# Sheet2.net
KiCad netlist of a schematic drawn in Altium Designer
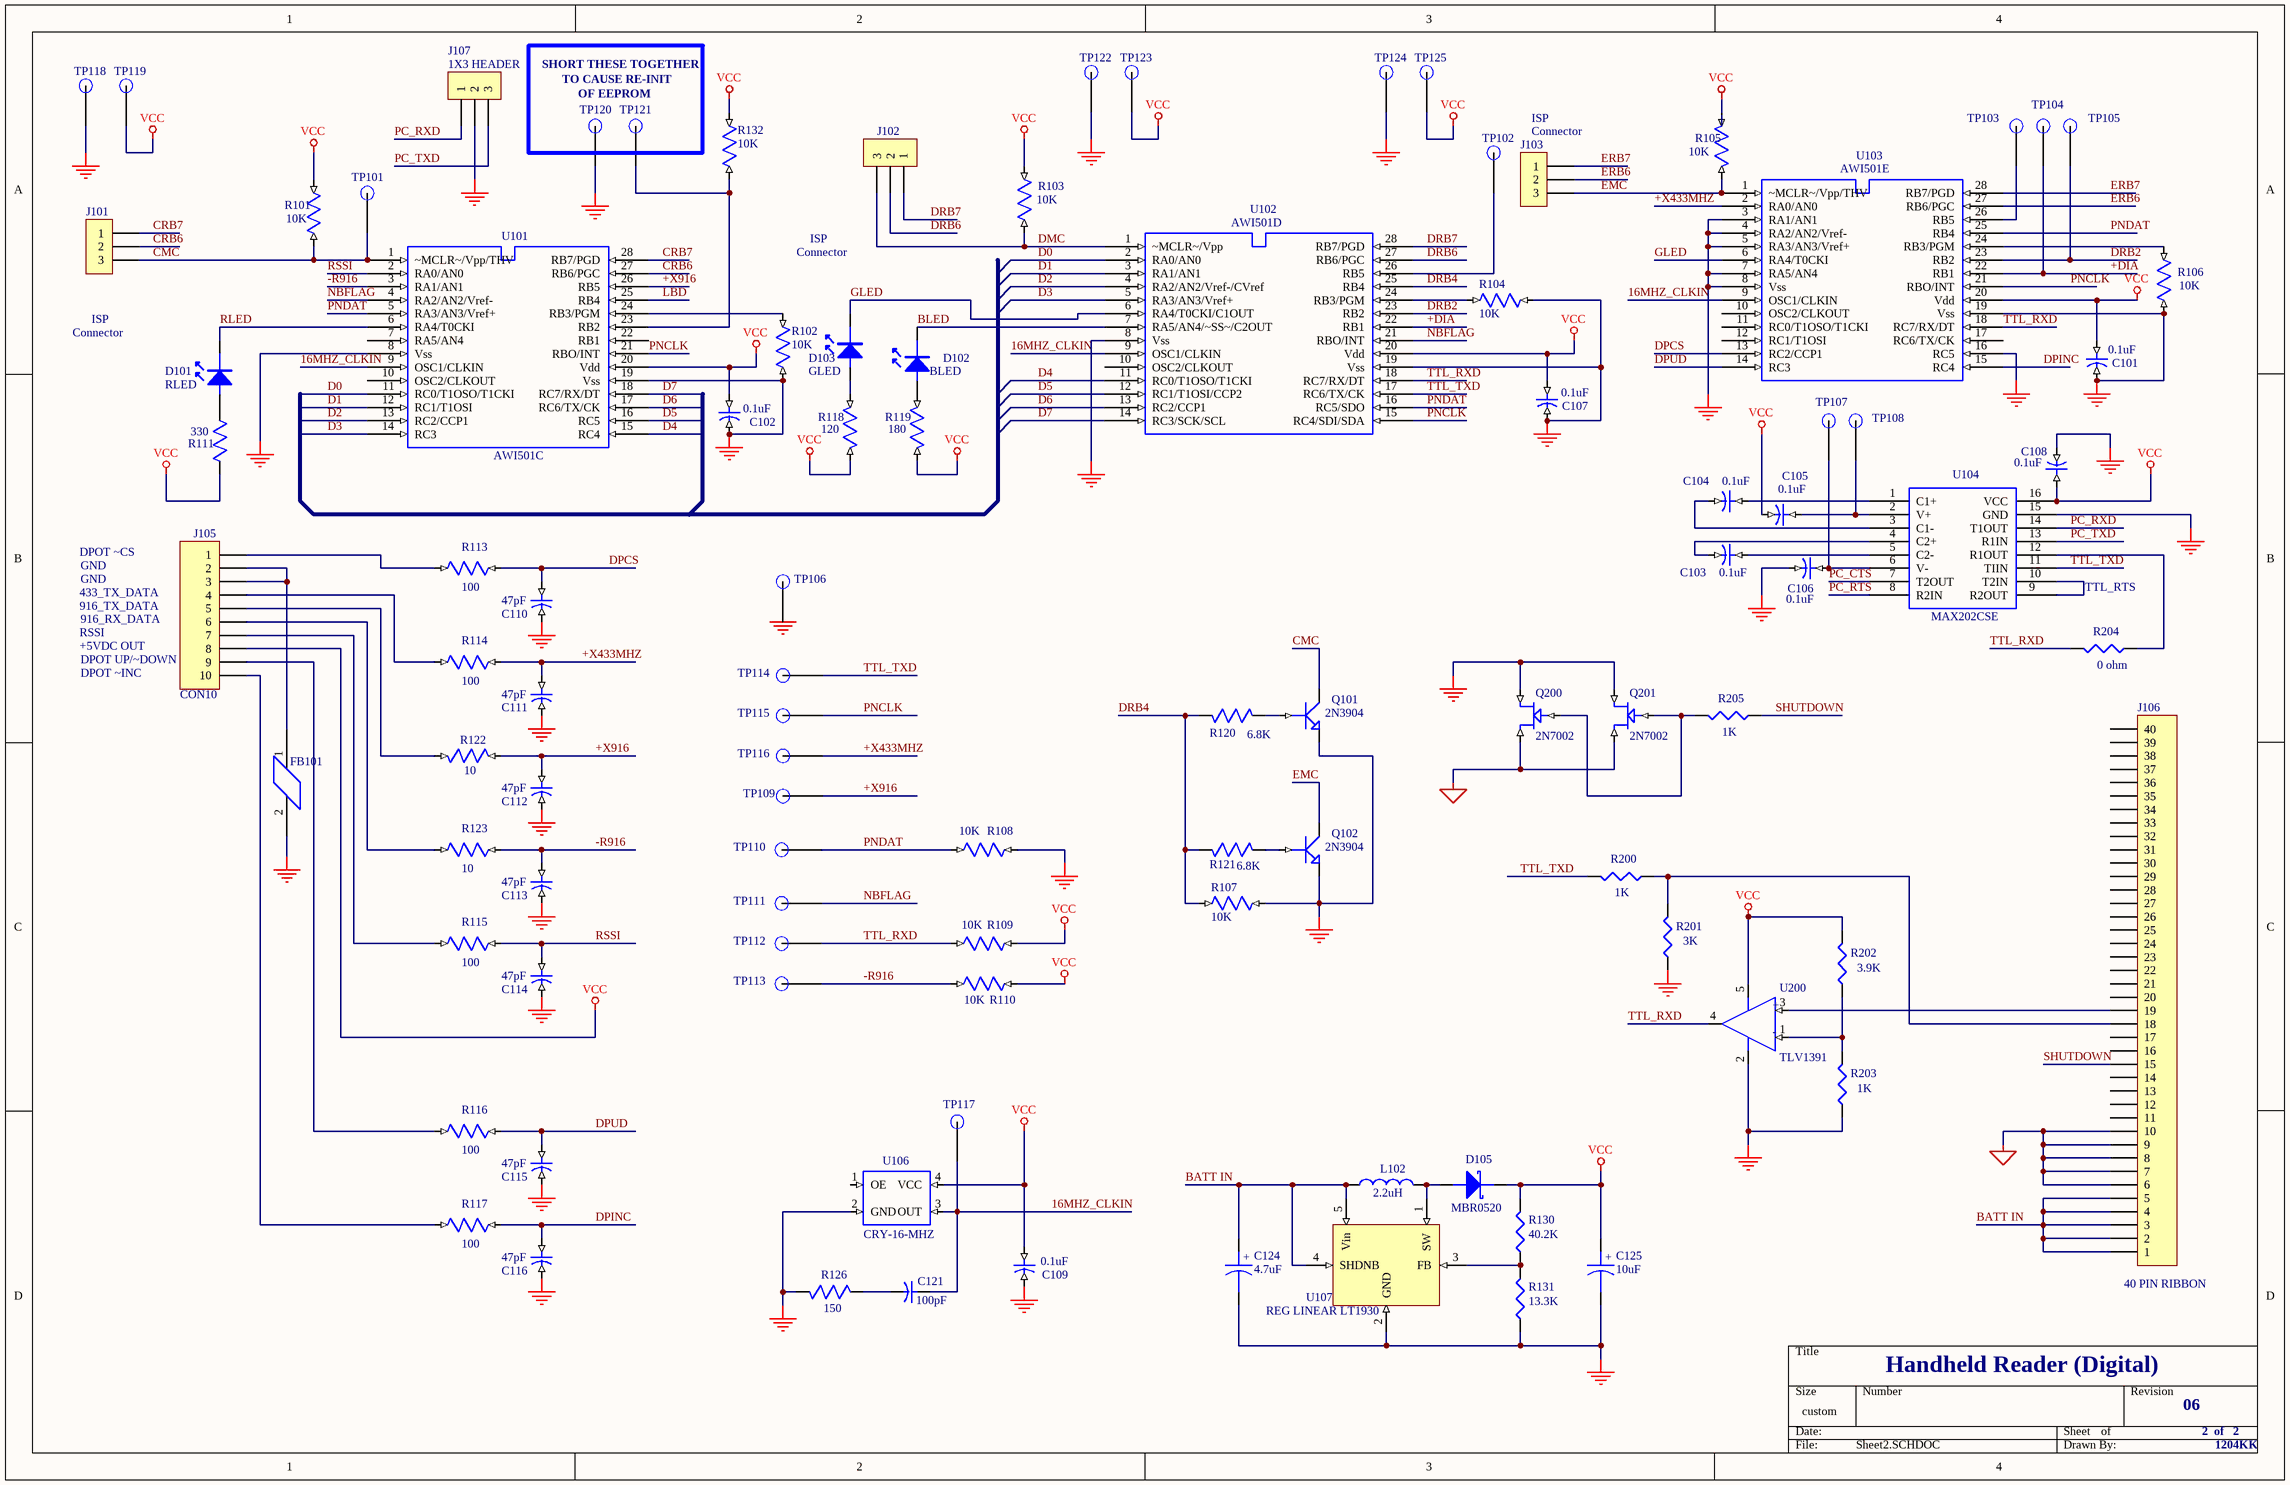
[diagram p0: Sheet2.SCHDOC]

(export (version "E")
  (design (tool "Eeschema 10.0.6"))
  (components
    (comp (ref "C101") (value "0.1uF") (footprint "0603") (libsource (lib "") (part "C_603_1")))
    (comp (ref "C102") (value "0.1uF") (footprint "0603") (libsource (lib "") (part "C_603_1")))
    (comp (ref "C103") (value "0.1uF") (footprint "0603") (libsource (lib "*") (part "C_603")))
    (comp (ref "C104") (value "0.1uF") (footprint "0603") (libsource (lib "*") (part "C_603")))
    (comp (ref "C105") (value "0.1uF") (footprint "0603") (libsource (lib "*") (part "C_603")))
    (comp (ref "C106") (value "0.1uF") (footprint "0603") (libsource (lib "*") (part "C_603")))
    (comp (ref "C107") (value "0.1uF") (footprint "0603") (libsource (lib "") (part "C_603_1")))
    (comp (ref "C108") (value "0.1uF") (footprint "0603") (libsource (lib "*") (part "C_603")))
    (comp (ref "C109") (value "0.1uF") (footprint "0603") (libsource (lib "*") (part "C_603")))
    (comp (ref "C110") (value "47pF") (footprint "0603") (libsource (lib "*") (part "C0603")))
    (comp (ref "C111") (value "47pF") (footprint "0603") (libsource (lib "*") (part "C0603")))
    (comp (ref "C112") (value "47pF") (footprint "0603") (libsource (lib "*") (part "C0603")))
    (comp (ref "C113") (value "47pF") (footprint "0603") (libsource (lib "*") (part "C0603")))
    (comp (ref "C114") (value "47pF") (footprint "0603") (libsource (lib "*") (part "C0603")))
    (comp (ref "C115") (value "47pF") (footprint "0603") (libsource (lib "*") (part "C0603")))
    (comp (ref "C116") (value "47pF") (footprint "0603") (libsource (lib "*") (part "C0603")))
    (comp (ref "C121") (value "100pF") (footprint "0603") (libsource (lib "*") (part "C_0603")))
    (comp (ref "C124")
      (value "4.7uF")
      (footprint "CAP A CASE")
      (description "Capacitor")
      (libsource (lib "*") (part "CAPACITOR POL"))
    )
    (comp (ref "C125")
      (value "10uF")
      (footprint "CAP A CASE")
      (description "Capacitor")
      (libsource (lib "*") (part "CAPACITOR POL"))
    )
    (comp (ref "D101") (value "RLED") (footprint "SOD123 DIODE") (libsource (lib "*") (part "LED")))
    (comp (ref "D102") (value "BLED") (footprint "SOD123 DIODE") (libsource (lib "*") (part "LED")))
    (comp (ref "D103") (value "GLED") (footprint "SOD123 DIODE") (libsource (lib "*") (part "LED")))
    (comp (ref "D105")
      (value "MBR0520")
      (footprint "SOD123")
      (description "Schottky Diode")
      (libsource (lib "*") (part "DIODE SCHOTTKY"))
    )
    (comp (ref "FB101") (value "FB 0603") (footprint "0603") (libsource (lib "*") (part "FB_0603")))
    (comp (ref "J101")
      (value "1X3 HEADER")
      (footprint "1X3 HEADER")
      (description "Connector")
      (libsource (lib "*") (part "CON3"))
    )
    (comp (ref "J102")
      (value "1X3 HEADER")
      (footprint "1X3 HEADER")
      (description "Connector")
      (libsource (lib "") (part "CON3_2"))
    )
    (comp (ref "J103")
      (value "1X3 HEADER")
      (footprint "1X3 HEADER")
      (description "Connector")
      (libsource (lib "*") (part "CON3"))
    )
    (comp (ref "J105")
      (value "CON10")
      (footprint "1X10 HEADER SPECIAL")
      (description "Connector")
      (libsource (lib "*") (part "CON10"))
    )
    (comp (ref "J106")
      (value "40 PIN RIBBON")
      (footprint "40 PIN RIBBON CONN")
      (description "Connector")
      (libsource (lib "*") (part "CON40"))
    )
    (comp (ref "J107")
      (value "1X3 HEADER")
      (footprint "1X3 HEADER")
      (description "Connector")
      (libsource (lib "") (part "CON3_1"))
    )
    (comp (ref "L102")
      (value "2.2uH")
      (footprint "COIL BOURNS SDR7030-330M")
      (libsource (lib "*") (part "INDUCTOR1"))
    )
    (comp (ref "Q101")
      (value "2N3904")
      (footprint "SOT23 TRANS")
      (description "NPN Transistor")
      (libsource (lib "*") (part "NPN1"))
    )
    (comp (ref "Q102")
      (value "2N3904")
      (footprint "SOT23 TRANS")
      (description "NPN Transistor")
      (libsource (lib "*") (part "NPN1"))
    )
    (comp (ref "Q200") (value "2N7002") (footprint "SOT23 FET") (libsource (lib "*") (part "JFET N")))
    (comp (ref "Q201") (value "2N7002") (footprint "SOT23 FET") (libsource (lib "*") (part "JFET N")))
    (comp (ref "R101") (value "10K") (footprint "0603") (libsource (lib "*") (part "R_603")))
    (comp (ref "R102") (value "10K") (footprint "0603") (libsource (lib "*") (part "R_603")))
    (comp (ref "R103") (value "10K") (footprint "0603") (libsource (lib "*") (part "R_603")))
    (comp (ref "R104") (value "10K") (footprint "0603") (libsource (lib "*") (part "R_603")))
    (comp (ref "R105") (value "10K") (footprint "0603") (libsource (lib "*") (part "R_603")))
    (comp (ref "R106") (value "10K") (footprint "0603") (libsource (lib "*") (part "R_603")))
    (comp (ref "R107") (value "10K") (footprint "0603") (libsource (lib "*") (part "R_603")))
    (comp (ref "R108") (value "10K") (footprint "0603") (libsource (lib "*") (part "R_603")))
    (comp (ref "R109") (value "10K") (footprint "0603") (libsource (lib "*") (part "R_603")))
    (comp (ref "R110") (value "10K") (footprint "0603") (libsource (lib "*") (part "R_603")))
    (comp (ref "R111") (value "330") (footprint "0603") (libsource (lib "*") (part "R_0603")))
    (comp (ref "R113") (value "100") (footprint "0603") (libsource (lib "*") (part "R0603")))
    (comp (ref "R114") (value "100") (footprint "0603") (libsource (lib "*") (part "R0603")))
    (comp (ref "R115") (value "100") (footprint "0603") (libsource (lib "*") (part "R0603")))
    (comp (ref "R116") (value "100") (footprint "0603") (libsource (lib "*") (part "R0603")))
    (comp (ref "R117") (value "100") (footprint "0603") (libsource (lib "*") (part "R0603")))
    (comp (ref "R118") (value "120") (footprint "0603") (libsource (lib "*") (part "R0402")))
    (comp (ref "R119") (value "180") (footprint "0603") (libsource (lib "*") (part "R0402")))
    (comp (ref "R120") (value "6.8K") (footprint "0603") (libsource (lib "*") (part "R_0603")))
    (comp (ref "R121") (value "6.8K") (footprint "0603") (libsource (lib "*") (part "R_0603")))
    (comp (ref "R122") (value "10") (footprint "0603") (libsource (lib "*") (part "R_603")))
    (comp (ref "R123") (value "10") (footprint "0603") (libsource (lib "*") (part "R0603")))
    (comp (ref "R126") (value "150") (footprint "0603") (libsource (lib "*") (part "R_0603")))
    (comp (ref "R130") (value "40.2K") (footprint "0603") (libsource (lib "*") (part "RES1")))
    (comp (ref "R131") (value "13.3K") (footprint "0603") (libsource (lib "*") (part "RES1")))
    (comp (ref "R132") (value "10K") (footprint "0603") (libsource (lib "*") (part "R_603")))
    (comp (ref "R200") (value "1K") (footprint "0603") (libsource (lib "*") (part "RES1")))
    (comp (ref "R201") (value "3K") (footprint "0603") (libsource (lib "*") (part "RES1")))
    (comp (ref "R202") (value "3.9K") (footprint "0603") (libsource (lib "*") (part "RES1")))
    (comp (ref "R203") (value "1K") (footprint "0603") (libsource (lib "*") (part "RES1")))
    (comp (ref "R204") (value "0 ohm") (footprint "0603") (libsource (lib "*") (part "RES1")))
    (comp (ref "R205") (value "1K") (footprint "0603") (libsource (lib "*") (part "RES1")))
    (comp (ref "TP101") (value "TP") (footprint "TEST POINT PAD") (libsource (lib "*") (part "TESTPOINT_1")))
    (comp (ref "TP102") (value "TP") (footprint "TEST POINT PAD") (libsource (lib "*") (part "TESTPOINT_1")))
    (comp (ref "TP103") (value "TP") (footprint "TEST POINT PAD") (libsource (lib "*") (part "TESTPOINT_1")))
    (comp (ref "TP104") (value "TP") (footprint "TEST POINT PAD") (libsource (lib "*") (part "TESTPOINT_1")))
    (comp (ref "TP105") (value "TP") (footprint "TEST POINT PAD") (libsource (lib "*") (part "TESTPOINT_1")))
    (comp (ref "TP106") (value "TP") (footprint "TEST POINT PAD") (libsource (lib "*") (part "TESTPOINT_1")))
    (comp (ref "TP107") (value "TP") (footprint "TEST POINT PAD") (libsource (lib "*") (part "TESTPOINT_1")))
    (comp (ref "TP108") (value "TP") (footprint "TEST POINT PAD") (libsource (lib "*") (part "TESTPOINT_1")))
    (comp (ref "TP109") (value "TP") (footprint "TEST POINT PAD") (libsource (lib "*") (part "TESTPOINT_1")))
    (comp (ref "TP110") (value "TP") (footprint "TEST POINT PAD") (libsource (lib "*") (part "TESTPOINT_1")))
    (comp (ref "TP111") (value "TP") (footprint "TEST POINT PAD") (libsource (lib "*") (part "TESTPOINT_1")))
    (comp (ref "TP112") (value "TP") (footprint "TEST POINT PAD") (libsource (lib "*") (part "TESTPOINT_1")))
    (comp (ref "TP113") (value "TP") (footprint "TEST POINT PAD") (libsource (lib "*") (part "TESTPOINT_1")))
    (comp (ref "TP114") (value "TP") (footprint "TEST POINT PAD") (libsource (lib "*") (part "TESTPOINT_1")))
    (comp (ref "TP115") (value "TP") (footprint "TEST POINT PAD") (libsource (lib "*") (part "TESTPOINT_1")))
    (comp (ref "TP116") (value "TP") (footprint "TEST POINT PAD") (libsource (lib "*") (part "TESTPOINT_1")))
    (comp (ref "TP117") (value "TP") (footprint "TEST POINT PAD") (libsource (lib "*") (part "TESTPOINT_1")))
    (comp (ref "TP118") (value "TP") (footprint "TEST POINT PAD") (libsource (lib "*") (part "TESTPOINT_1")))
    (comp (ref "TP119") (value "TP") (footprint "TEST POINT PAD") (libsource (lib "*") (part "TESTPOINT_1")))
    (comp (ref "TP120") (value "TP") (footprint "TEST POINT PAD") (libsource (lib "*") (part "TESTPOINT_1")))
    (comp (ref "TP121") (value "TP") (footprint "TEST POINT PAD") (libsource (lib "*") (part "TESTPOINT_1")))
    (comp (ref "TP122") (value "TP") (footprint "TEST POINT PAD") (libsource (lib "*") (part "TESTPOINT_1")))
    (comp (ref "TP123") (value "TP") (footprint "TEST POINT PAD") (libsource (lib "*") (part "TESTPOINT_1")))
    (comp (ref "TP124") (value "TP") (footprint "TEST POINT PAD") (libsource (lib "*") (part "TESTPOINT_1")))
    (comp (ref "TP125") (value "TP") (footprint "TEST POINT PAD") (libsource (lib "*") (part "TESTPOINT_1")))
    (comp (ref "U101") (value "AWI501C") (footprint "SSOP28") (libsource (lib "*") (part "PIC16F870")))
    (comp (ref "U102") (value "AWI501D") (footprint "SSOP28") (libsource (lib "*") (part "PIC16F876A")))
    (comp (ref "U103") (value "AWI501E") (footprint "SSOP28") (libsource (lib "*") (part "PIC16F870")))
    (comp (ref "U104") (value "MAX202CSE") (footprint "SO16") (libsource (lib "*") (part "MAX202CSE")))
    (comp (ref "U106")
      (value "CRY-16-MHZ")
      (footprint "SMT OSCILLATOR")
      (libsource (lib "*") (part "CRY-SMD-5-7"))
    )
    (comp (ref "U107")
      (value "REG LINEAR LT1930")
      (footprint "SOT23-5A")
      (libsource (lib "*") (part "REG LINEAR LT1930"))
    )
    (comp (ref "U200") (value "TLV1391") (footprint "SOT25") (libsource (lib "*") (part "TLV1391")))
  )
  (nets
    (net (code "1") (name "/+DIA") (class "Default")
      (node (ref "TP104") (pin "1") (pinfunction "TP_1") (pintype "passive"))
      (node (ref "U102") (pin "22") (pinfunction "RB1_22") (pintype "input"))
      (node (ref "U103") (pin "22") (pinfunction "RB1_22") (pintype "input"))
    )
    (net (code "2") (name "/+X433MHZ") (class "Default")
      (node (ref "C111") (pin "1") (pinfunction "A_1") (pintype "input"))
      (node (ref "R114") (pin "2") (pinfunction "B_2") (pintype "input"))
      (node (ref "TP116") (pin "1") (pinfunction "TP_1") (pintype "passive"))
      (node (ref "U103") (pin "2") (pinfunction "RA0/AN0_2") (pintype "input"))
    )
    (net (code "3") (name "/+X916") (class "Default")
      (node (ref "C112") (pin "1") (pinfunction "A_1") (pintype "input"))
      (node (ref "R122") (pin "1") (pinfunction "A_1") (pintype "input"))
      (node (ref "TP109") (pin "1") (pinfunction "TP_1") (pintype "passive"))
      (node (ref "U101") (pin "26") (pinfunction "RB5_26") (pintype "input"))
    )
    (net (code "4") (name "/-R916") (class "Default")
      (node (ref "C113") (pin "1") (pinfunction "A_1") (pintype "input"))
      (node (ref "R110") (pin "2") (pinfunction "B_2") (pintype "input"))
      (node (ref "R123") (pin "2") (pinfunction "B_2") (pintype "input"))
      (node (ref "TP113") (pin "1") (pinfunction "TP_1") (pintype "passive"))
      (node (ref "U101") (pin "3") (pinfunction "RA1/AN1_3") (pintype "input"))
    )
    (net (code "5") (name "/16MHZ_CLKIN") (class "Default")
      (node (ref "C121") (pin "1") (pinfunction "A_1") (pintype "passive"))
      (node (ref "TP117") (pin "1") (pinfunction "TP_1") (pintype "passive"))
      (node (ref "U101") (pin "9") (pinfunction "OSC1/CLKIN_9") (pintype "input"))
      (node (ref "U102") (pin "9") (pinfunction "OSC1/CLKIN_9") (pintype "input"))
      (node (ref "U103") (pin "9") (pinfunction "OSC1/CLKIN_9") (pintype "input"))
      (node (ref "U106") (pin "3") (pinfunction "OUT_3") (pintype "input"))
    )
    (net (code "6") (name "/BATT IN") (class "Default")
      (node (ref "C124") (pin "1") (pinfunction "1_1") (pintype "passive"))
      (node (ref "J106") (pin "1") (pinfunction "1_1") (pintype "passive"))
      (node (ref "J106") (pin "2") (pinfunction "2_2") (pintype "passive"))
      (node (ref "J106") (pin "3") (pinfunction "3_3") (pintype "passive"))
      (node (ref "J106") (pin "4") (pinfunction "4_4") (pintype "passive"))
      (node (ref "J106") (pin "5") (pinfunction "5_5") (pintype "passive"))
      (node (ref "L102") (pin "1") (pinfunction "1_1") (pintype "passive"))
      (node (ref "U107") (pin "4") (pinfunction "SHDNB_4") (pintype "input"))
      (node (ref "U107") (pin "5") (pinfunction "Vin_5") (pintype "input"))
    )
    (net (code "7") (name "/BLED") (class "Default")
      (node (ref "D102") (pin "K") (pinfunction "K_K") (pintype "passive"))
      (node (ref "U102") (pin "7") (pinfunction "RA5/AN4/~SS~/C2OUT_7") (pintype "input"))
    )
    (net (code "8") (name "/CMC") (class "Default")
      (node (ref "J101") (pin "3") (pinfunction "3_3") (pintype "passive"))
      (node (ref "Q101") (pin "C") (pinfunction "C_C") (pintype "passive"))
      (node (ref "R101") (pin "2") (pinfunction "B_2") (pintype "input"))
      (node (ref "TP101") (pin "1") (pinfunction "TP_1") (pintype "passive"))
      (node (ref "U101") (pin "1") (pinfunction "~MCLR~/Vpp/THV_1") (pintype "input"))
    )
    (net (code "9") (name "/CRB6") (class "Default")
      (node (ref "J101") (pin "2") (pinfunction "2_2") (pintype "passive"))
      (node (ref "U101") (pin "27") (pinfunction "RB6/PGC_27") (pintype "input"))
    )
    (net (code "10") (name "/CRB7") (class "Default")
      (node (ref "J101") (pin "1") (pinfunction "1_1") (pintype "passive"))
      (node (ref "U101") (pin "28") (pinfunction "RB7/PGD_28") (pintype "input"))
    )
    (net (code "11") (name "/D0") (class "Default")
      (node (ref "U101") (pin "11") (pinfunction "RC0/T1OSO/T1CKI_11") (pintype "input"))
      (node (ref "U102") (pin "2") (pinfunction "RA0/AN0_2") (pintype "input"))
    )
    (net (code "12") (name "/D1") (class "Default")
      (node (ref "U101") (pin "12") (pinfunction "RC1/T1OSI_12") (pintype "input"))
      (node (ref "U102") (pin "3") (pinfunction "RA1/AN1_3") (pintype "input"))
    )
    (net (code "13") (name "/D2") (class "Default")
      (node (ref "U101") (pin "13") (pinfunction "RC2/CCP1_13") (pintype "input"))
      (node (ref "U102") (pin "4") (pinfunction "RA2/AN2/Vref-/CVref_4") (pintype "input"))
    )
    (net (code "14") (name "/D3") (class "Default")
      (node (ref "U101") (pin "14") (pinfunction "RC3_14") (pintype "input"))
      (node (ref "U102") (pin "5") (pinfunction "RA3/AN3/Vref+_5") (pintype "input"))
    )
    (net (code "15") (name "/D4") (class "Default")
      (node (ref "U101") (pin "15") (pinfunction "RC4_15") (pintype "input"))
      (node (ref "U102") (pin "11") (pinfunction "RC0/T1OSO/T1CKI_11") (pintype "input"))
    )
    (net (code "16") (name "/D5") (class "Default")
      (node (ref "U101") (pin "16") (pinfunction "RC5_16") (pintype "input"))
      (node (ref "U102") (pin "12") (pinfunction "RC1/T1OSI/CCP2_12") (pintype "input"))
    )
    (net (code "17") (name "/D6") (class "Default")
      (node (ref "U101") (pin "17") (pinfunction "RC6/TX/CK_17") (pintype "input"))
      (node (ref "U102") (pin "13") (pinfunction "RC2/CCP1_13") (pintype "input"))
    )
    (net (code "18") (name "/D7") (class "Default")
      (node (ref "U101") (pin "18") (pinfunction "RC7/RX/DT_18") (pintype "input"))
      (node (ref "U102") (pin "14") (pinfunction "RC3/SCK/SCL_14") (pintype "input"))
    )
    (net (code "19") (name "/DMC") (class "Default")
      (node (ref "J102") (pin "3") (pinfunction "3_3") (pintype "passive"))
      (node (ref "R103") (pin "2") (pinfunction "B_2") (pintype "input"))
      (node (ref "U102") (pin "1") (pinfunction "~MCLR~/Vpp_1") (pintype "input"))
    )
    (net (code "20") (name "/DPCS") (class "Default")
      (node (ref "C110") (pin "1") (pinfunction "A_1") (pintype "input"))
      (node (ref "R113") (pin "2") (pinfunction "B_2") (pintype "input"))
      (node (ref "U103") (pin "13") (pinfunction "RC2/CCP1_13") (pintype "input"))
    )
    (net (code "21") (name "/DPINC") (class "Default")
      (node (ref "C116") (pin "1") (pinfunction "A_1") (pintype "input"))
      (node (ref "R117") (pin "2") (pinfunction "B_2") (pintype "input"))
      (node (ref "U103") (pin "15") (pinfunction "RC4_15") (pintype "input"))
    )
    (net (code "22") (name "/DPUD") (class "Default")
      (node (ref "C115") (pin "1") (pinfunction "A_1") (pintype "input"))
      (node (ref "R116") (pin "2") (pinfunction "B_2") (pintype "input"))
      (node (ref "U103") (pin "14") (pinfunction "RC3_14") (pintype "input"))
    )
    (net (code "23") (name "/DRB2") (class "Default")
      (node (ref "TP105") (pin "1") (pinfunction "TP_1") (pintype "passive"))
      (node (ref "U102") (pin "23") (pinfunction "RB2_23") (pintype "input"))
      (node (ref "U103") (pin "23") (pinfunction "RB2_23") (pintype "input"))
    )
    (net (code "24") (name "/DRB4") (class "Default")
      (node (ref "R107") (pin "1") (pinfunction "A_1") (pintype "input"))
      (node (ref "R120") (pin "1") (pinfunction "A_1") (pintype "passive"))
      (node (ref "R121") (pin "1") (pinfunction "A_1") (pintype "passive"))
      (node (ref "U102") (pin "25") (pinfunction "RB4_25") (pintype "input"))
    )
    (net (code "25") (name "/DRB6") (class "Default")
      (node (ref "J102") (pin "2") (pinfunction "2_2") (pintype "passive"))
      (node (ref "U102") (pin "27") (pinfunction "RB6/PGC_27") (pintype "input"))
    )
    (net (code "26") (name "/DRB7") (class "Default")
      (node (ref "J102") (pin "1") (pinfunction "1_1") (pintype "passive"))
      (node (ref "U102") (pin "28") (pinfunction "RB7/PGD_28") (pintype "input"))
    )
    (net (code "27") (name "/EMC") (class "Default")
      (node (ref "J103") (pin "3") (pinfunction "3_3") (pintype "passive"))
      (node (ref "Q102") (pin "C") (pinfunction "C_C") (pintype "passive"))
      (node (ref "R105") (pin "2") (pinfunction "B_2") (pintype "input"))
      (node (ref "U103") (pin "1") (pinfunction "~MCLR~/Vpp/THV_1") (pintype "input"))
    )
    (net (code "28") (name "/ERB6") (class "Default")
      (node (ref "J103") (pin "2") (pinfunction "2_2") (pintype "passive"))
      (node (ref "U103") (pin "27") (pinfunction "RB6/PGC_27") (pintype "input"))
    )
    (net (code "29") (name "/ERB7") (class "Default")
      (node (ref "J103") (pin "1") (pinfunction "1_1") (pintype "passive"))
      (node (ref "U103") (pin "28") (pinfunction "RB7/PGD_28") (pintype "input"))
    )
    (net (code "30") (name "/GLED") (class "Default")
      (node (ref "D103") (pin "K") (pinfunction "K_K") (pintype "passive"))
      (node (ref "U102") (pin "6") (pinfunction "RA4/T0CKI/C1OUT_6") (pintype "input"))
      (node (ref "U103") (pin "6") (pinfunction "RA4/T0CKI_6") (pintype "input"))
    )
    (net (code "31") (name "/LBD") (class "Default")
      (node (ref "U101") (pin "25") (pinfunction "RB4_25") (pintype "input"))
    )
    (net (code "32") (name "/NBFLAG") (class "Default")
      (node (ref "TP111") (pin "1") (pinfunction "TP_1") (pintype "passive"))
      (node (ref "U101") (pin "4") (pinfunction "RA2/AN2/Vref-_4") (pintype "input"))
      (node (ref "U102") (pin "21") (pinfunction "RBO/INT_21") (pintype "input"))
    )
    (net (code "33") (name "/PC_CTS") (class "Default")
      (node (ref "U104") (pin "7") (pinfunction "T2OUT_7") (pintype "passive"))
    )
    (net (code "34") (name "/PC_RTS") (class "Default")
      (node (ref "U104") (pin "8") (pinfunction "R2IN_8") (pintype "passive"))
    )
    (net (code "35") (name "/PC_RXD") (class "Default")
      (node (ref "J107") (pin "1") (pinfunction "1_1") (pintype "passive"))
      (node (ref "U104") (pin "14") (pinfunction "T1OUT_14") (pintype "passive"))
    )
    (net (code "36") (name "/PC_TXD") (class "Default")
      (node (ref "J107") (pin "3") (pinfunction "3_3") (pintype "passive"))
      (node (ref "U104") (pin "13") (pinfunction "R1IN_13") (pintype "passive"))
    )
    (net (code "37") (name "/PNCLK") (class "Default")
      (node (ref "TP115") (pin "1") (pinfunction "TP_1") (pintype "passive"))
      (node (ref "U101") (pin "21") (pinfunction "RBO/INT_21") (pintype "input"))
      (node (ref "U102") (pin "15") (pinfunction "RC4/SDI/SDA_15") (pintype "input"))
      (node (ref "U103") (pin "21") (pinfunction "RBO/INT_21") (pintype "input"))
    )
    (net (code "38") (name "/PNDAT") (class "Default")
      (node (ref "R108") (pin "2") (pinfunction "B_2") (pintype "input"))
      (node (ref "TP110") (pin "1") (pinfunction "TP_1") (pintype "passive"))
      (node (ref "U101") (pin "5") (pinfunction "RA3/AN3/Vref+_5") (pintype "input"))
      (node (ref "U102") (pin "16") (pinfunction "RC5/SDO_16") (pintype "input"))
      (node (ref "U103") (pin "25") (pinfunction "RB4_25") (pintype "input"))
    )
    (net (code "39") (name "/RLED") (class "Default")
      (node (ref "D101") (pin "K") (pinfunction "K_K") (pintype "passive"))
      (node (ref "U101") (pin "6") (pinfunction "RA4/T0CKI_6") (pintype "input"))
    )
    (net (code "40") (name "/RSSI") (class "Default")
      (node (ref "C114") (pin "1") (pinfunction "A_1") (pintype "input"))
      (node (ref "R115") (pin "2") (pinfunction "B_2") (pintype "input"))
      (node (ref "U101") (pin "2") (pinfunction "RA0/AN0_2") (pintype "input"))
    )
    (net (code "41") (name "/SHUTDOWN") (class "Default")
      (node (ref "J106") (pin "15") (pinfunction "15_15") (pintype "passive"))
      (node (ref "R205") (pin "1") (pinfunction "1_1") (pintype "passive"))
    )
    (net (code "42") (name "/TTL_RXD") (class "Default")
      (node (ref "R109") (pin "2") (pinfunction "B_2") (pintype "input"))
      (node (ref "R204") (pin "2") (pinfunction "2_2") (pintype "passive"))
      (node (ref "TP112") (pin "1") (pinfunction "TP_1") (pintype "passive"))
      (node (ref "U102") (pin "18") (pinfunction "RC7/RX/DT_18") (pintype "input"))
      (node (ref "U103") (pin "18") (pinfunction "RC7/RX/DT_18") (pintype "input"))
      (node (ref "U200") (pin "4") (pinfunction "OUT_4") (pintype "open_collector"))
    )
    (net (code "43") (name "/TTL_TXD") (class "Default")
      (node (ref "R200") (pin "2") (pinfunction "2_2") (pintype "passive"))
      (node (ref "TP114") (pin "1") (pinfunction "TP_1") (pintype "passive"))
      (node (ref "U102") (pin "17") (pinfunction "RC6/TX/CK_17") (pintype "input"))
      (node (ref "U104") (pin "11") (pinfunction "TIIN_11") (pintype "passive"))
    )
    (net (code "44") (name "GND1") (class "Default")
      (node (ref "J106") (pin "10") (pinfunction "10_10") (pintype "passive"))
      (node (ref "J106") (pin "6") (pinfunction "6_6") (pintype "passive"))
      (node (ref "J106") (pin "7") (pinfunction "7_7") (pintype "passive"))
      (node (ref "J106") (pin "8") (pinfunction "8_8") (pintype "passive"))
      (node (ref "J106") (pin "9") (pinfunction "9_9") (pintype "passive"))
      (node (ref "Q200") (pin "S") (pinfunction "S_S") (pintype "input"))
      (node (ref "Q201") (pin "S") (pinfunction "S_S") (pintype "input"))
    )
    (net (code "45") (name "GND_COM") (class "Default")
      (node (ref "C101") (pin "2") (pinfunction "B_2") (pintype "input"))
      (node (ref "C102") (pin "2") (pinfunction "B_2") (pintype "input"))
      (node (ref "C106") (pin "2") (pinfunction "B_2") (pintype "input"))
      (node (ref "C107") (pin "2") (pinfunction "B_2") (pintype "input"))
      (node (ref "C108") (pin "2") (pinfunction "B_2") (pintype "input"))
      (node (ref "C109") (pin "2") (pinfunction "B_2") (pintype "input"))
      (node (ref "C110") (pin "2") (pinfunction "B_2") (pintype "input"))
      (node (ref "C111") (pin "2") (pinfunction "B_2") (pintype "input"))
      (node (ref "C112") (pin "2") (pinfunction "B_2") (pintype "input"))
      (node (ref "C113") (pin "2") (pinfunction "B_2") (pintype "input"))
      (node (ref "C114") (pin "2") (pinfunction "B_2") (pintype "input"))
      (node (ref "C115") (pin "2") (pinfunction "B_2") (pintype "input"))
      (node (ref "C116") (pin "2") (pinfunction "B_2") (pintype "input"))
      (node (ref "C124") (pin "2") (pinfunction "2_2") (pintype "passive"))
      (node (ref "C125") (pin "2") (pinfunction "2_2") (pintype "passive"))
      (node (ref "FB101") (pin "2") (pinfunction "1_2") (pintype "passive"))
      (node (ref "J107") (pin "2") (pinfunction "2_2") (pintype "passive"))
      (node (ref "Q101") (pin "E") (pinfunction "E_E") (pintype "passive"))
      (node (ref "Q102") (pin "E") (pinfunction "E_E") (pintype "passive"))
      (node (ref "Q200") (pin "D") (pinfunction "D_D") (pintype "input"))
      (node (ref "Q201") (pin "D") (pinfunction "D_D") (pintype "input"))
      (node (ref "R102") (pin "2") (pinfunction "B_2") (pintype "input"))
      (node (ref "R104") (pin "1") (pinfunction "A_1") (pintype "input"))
      (node (ref "R106") (pin "2") (pinfunction "B_2") (pintype "input"))
      (node (ref "R107") (pin "2") (pinfunction "B_2") (pintype "input"))
      (node (ref "R108") (pin "1") (pinfunction "A_1") (pintype "input"))
      (node (ref "R126") (pin "2") (pinfunction "B_2") (pintype "passive"))
      (node (ref "R131") (pin "1") (pinfunction "1_1") (pintype "passive"))
      (node (ref "R201") (pin "1") (pinfunction "1_1") (pintype "passive"))
      (node (ref "R203") (pin "1") (pinfunction "1_1") (pintype "passive"))
      (node (ref "TP106") (pin "1") (pinfunction "TP_1") (pintype "passive"))
      (node (ref "TP118") (pin "1") (pinfunction "TP_1") (pintype "passive"))
      (node (ref "TP120") (pin "1") (pinfunction "TP_1") (pintype "passive"))
      (node (ref "TP122") (pin "1") (pinfunction "TP_1") (pintype "passive"))
      (node (ref "TP124") (pin "1") (pinfunction "TP_1") (pintype "passive"))
      (node (ref "U101") (pin "19") (pinfunction "Vss_19") (pintype "input"))
      (node (ref "U101") (pin "8") (pinfunction "Vss_8") (pintype "input"))
      (node (ref "U102") (pin "19") (pinfunction "Vss_19") (pintype "input"))
      (node (ref "U102") (pin "8") (pinfunction "Vss_8") (pintype "input"))
      (node (ref "U103") (pin "16") (pinfunction "RC5_16") (pintype "input"))
      (node (ref "U103") (pin "19") (pinfunction "Vss_19") (pintype "input"))
      (node (ref "U103") (pin "3") (pinfunction "RA1/AN1_3") (pintype "input"))
      (node (ref "U103") (pin "4") (pinfunction "RA2/AN2/Vref-_4") (pintype "input"))
      (node (ref "U103") (pin "5") (pinfunction "RA3/AN3/Vref+_5") (pintype "input"))
      (node (ref "U103") (pin "7") (pinfunction "RA5/AN4_7") (pintype "input"))
      (node (ref "U103") (pin "8") (pinfunction "Vss_8") (pintype "input"))
      (node (ref "U104") (pin "15") (pinfunction "GND_15") (pintype "passive"))
      (node (ref "U106") (pin "2") (pinfunction "GND_2") (pintype "input"))
      (node (ref "U107") (pin "2") (pinfunction "GND_2") (pintype "input"))
      (node (ref "U200") (pin "2") (pinfunction "VSS_2") (pintype "power_in"))
    )
    (net (code "46") (name "Net-(C103-A)") (class "Default")
      (node (ref "C103") (pin "1") (pinfunction "A_1") (pintype "input"))
      (node (ref "U104") (pin "5") (pinfunction "C2-_5") (pintype "passive"))
    )
    (net (code "47") (name "Net-(C103-B)") (class "Default")
      (node (ref "C103") (pin "2") (pinfunction "B_2") (pintype "input"))
      (node (ref "U104") (pin "4") (pinfunction "C2+_4") (pintype "passive"))
    )
    (net (code "48") (name "Net-(C104-A)") (class "Default")
      (node (ref "C104") (pin "1") (pinfunction "A_1") (pintype "input"))
      (node (ref "U104") (pin "1") (pinfunction "C1+_1") (pintype "passive"))
    )
    (net (code "49") (name "Net-(C104-B)") (class "Default")
      (node (ref "C104") (pin "2") (pinfunction "B_2") (pintype "input"))
      (node (ref "U104") (pin "3") (pinfunction "C1-_3") (pintype "passive"))
    )
    (net (code "50") (name "Net-(C105-A)") (class "Default")
      (node (ref "C105") (pin "1") (pinfunction "A_1") (pintype "input"))
      (node (ref "TP108") (pin "1") (pinfunction "TP_1") (pintype "passive"))
      (node (ref "U104") (pin "2") (pinfunction "V+_2") (pintype "passive"))
    )
    (net (code "51") (name "Net-(C106-A)") (class "Default")
      (node (ref "C106") (pin "1") (pinfunction "A_1") (pintype "input"))
      (node (ref "TP107") (pin "1") (pinfunction "TP_1") (pintype "passive"))
      (node (ref "U104") (pin "6") (pinfunction "V-_6") (pintype "passive"))
    )
    (net (code "52") (name "Net-(C121-B)") (class "Default")
      (node (ref "C121") (pin "2") (pinfunction "B_2") (pintype "passive"))
      (node (ref "R126") (pin "1") (pinfunction "A_1") (pintype "passive"))
    )
    (net (code "53") (name "Net-(FB101-2)") (class "Default")
      (node (ref "FB101") (pin "1") (pinfunction "2_1") (pintype "passive"))
      (node (ref "J105") (pin "2") (pinfunction "2_2") (pintype "passive"))
      (node (ref "J105") (pin "3") (pinfunction "3_3") (pintype "passive"))
    )
    (net (code "54") (name "Net-(J106-Pad18)") (class "Default")
      (node (ref "J106") (pin "18") (pinfunction "18_18") (pintype "passive"))
      (node (ref "R200") (pin "1") (pinfunction "1_1") (pintype "passive"))
      (node (ref "R201") (pin "2") (pinfunction "2_2") (pintype "passive"))
    )
    (net (code "55") (name "Net-(Q200-PadG)") (class "Default")
      (node (ref "Q200") (pin "G") (pinfunction "G_G") (pintype "input"))
      (node (ref "Q201") (pin "G") (pinfunction "G_G") (pintype "input"))
      (node (ref "R205") (pin "2") (pinfunction "2_2") (pintype "passive"))
    )
    (net (code "56") (name "Net-(R102-A)") (class "Default")
      (node (ref "R102") (pin "1") (pinfunction "A_1") (pintype "input"))
      (node (ref "U101") (pin "24") (pinfunction "RB3/PGM_24") (pintype "input"))
    )
    (net (code "57") (name "Net-(R104-B)") (class "Default")
      (node (ref "R104") (pin "2") (pinfunction "B_2") (pintype "input"))
      (node (ref "U102") (pin "24") (pinfunction "RB3/PGM_24") (pintype "input"))
    )
    (net (code "58") (name "Net-(R106-A)") (class "Default")
      (node (ref "R106") (pin "1") (pinfunction "A_1") (pintype "input"))
      (node (ref "U103") (pin "24") (pinfunction "RB3/PGM_24") (pintype "input"))
    )
    (net (code "59") (name "Net-(R111-B)") (class "Default")
      (node (ref "D101") (pin "A") (pinfunction "A_A") (pintype "passive"))
      (node (ref "R111") (pin "2") (pinfunction "B_2") (pintype "passive"))
    )
    (net (code "60") (name "Net-(R113-A)") (class "Default")
      (node (ref "J105") (pin "1") (pinfunction "1_1") (pintype "passive"))
      (node (ref "R113") (pin "1") (pinfunction "A_1") (pintype "input"))
    )
    (net (code "61") (name "Net-(R114-A)") (class "Default")
      (node (ref "J105") (pin "4") (pinfunction "4_4") (pintype "passive"))
      (node (ref "R114") (pin "1") (pinfunction "A_1") (pintype "input"))
    )
    (net (code "62") (name "Net-(R115-A)") (class "Default")
      (node (ref "J105") (pin "7") (pinfunction "7_7") (pintype "passive"))
      (node (ref "R115") (pin "1") (pinfunction "A_1") (pintype "input"))
    )
    (net (code "63") (name "Net-(R116-A)") (class "Default")
      (node (ref "J105") (pin "9") (pinfunction "9_9") (pintype "passive"))
      (node (ref "R116") (pin "1") (pinfunction "A_1") (pintype "input"))
    )
    (net (code "64") (name "Net-(R117-A)") (class "Default")
      (node (ref "J105") (pin "10") (pinfunction "10_10") (pintype "passive"))
      (node (ref "R117") (pin "1") (pinfunction "A_1") (pintype "input"))
    )
    (net (code "65") (name "Net-(R118-B)") (class "Default")
      (node (ref "D103") (pin "A") (pinfunction "A_A") (pintype "passive"))
      (node (ref "R118") (pin "2") (pinfunction "B_2") (pintype "input"))
    )
    (net (code "66") (name "Net-(R119-B)") (class "Default")
      (node (ref "D102") (pin "A") (pinfunction "A_A") (pintype "passive"))
      (node (ref "R119") (pin "2") (pinfunction "B_2") (pintype "input"))
    )
    (net (code "67") (name "Net-(R120-B)") (class "Default")
      (node (ref "Q101") (pin "B") (pinfunction "B_B") (pintype "input"))
      (node (ref "R120") (pin "2") (pinfunction "B_2") (pintype "passive"))
    )
    (net (code "68") (name "Net-(R121-B)") (class "Default")
      (node (ref "Q102") (pin "B") (pinfunction "B_B") (pintype "input"))
      (node (ref "R121") (pin "2") (pinfunction "B_2") (pintype "passive"))
    )
    (net (code "69") (name "Net-(R122-B)") (class "Default")
      (node (ref "J105") (pin "5") (pinfunction "5_5") (pintype "passive"))
      (node (ref "R122") (pin "2") (pinfunction "B_2") (pintype "input"))
    )
    (net (code "70") (name "Net-(R123-A)") (class "Default")
      (node (ref "J105") (pin "6") (pinfunction "6_6") (pintype "passive"))
      (node (ref "R123") (pin "1") (pinfunction "A_1") (pintype "input"))
    )
    (net (code "71") (name "Net-(R132-B)") (class "Default")
      (node (ref "R132") (pin "2") (pinfunction "B_2") (pintype "input"))
      (node (ref "TP121") (pin "1") (pinfunction "TP_1") (pintype "passive"))
      (node (ref "U101") (pin "23") (pinfunction "RB2_23") (pintype "input"))
    )
    (net (code "72") (name "Net-(TP102-TP)") (class "Default")
      (node (ref "TP102") (pin "1") (pinfunction "TP_1") (pintype "passive"))
      (node (ref "U102") (pin "26") (pinfunction "RB5_26") (pintype "input"))
    )
    (net (code "73") (name "Net-(TP103-TP)") (class "Default")
      (node (ref "TP103") (pin "1") (pinfunction "TP_1") (pintype "passive"))
      (node (ref "U103") (pin "26") (pinfunction "RB5_26") (pintype "input"))
    )
    (net (code "74") (name "Net-(U104-R1OUT)") (class "Default")
      (node (ref "R204") (pin "1") (pinfunction "1_1") (pintype "passive"))
      (node (ref "U104") (pin "12") (pinfunction "R1OUT_12") (pintype "passive"))
    )
    (net (code "75") (name "Net-(U104-R2OUT)") (class "Default")
      (node (ref "U104") (pin "10") (pinfunction "T2IN_10") (pintype "passive"))
      (node (ref "U104") (pin "9") (pinfunction "R2OUT_9") (pintype "passive"))
    )
    (net (code "76") (name "Net-(U107-FB)") (class "Default")
      (node (ref "R130") (pin "1") (pinfunction "1_1") (pintype "passive"))
      (node (ref "R131") (pin "2") (pinfunction "2_2") (pintype "passive"))
      (node (ref "U107") (pin "3") (pinfunction "FB_3") (pintype "input"))
    )
    (net (code "77") (name "Net-(U107-SW)") (class "Default")
      (node (ref "D105") (pin "A") (pinfunction "A_A") (pintype "passive"))
      (node (ref "L102") (pin "2") (pinfunction "2_2") (pintype "passive"))
      (node (ref "U107") (pin "1") (pinfunction "SW_1") (pintype "input"))
    )
    (net (code "78") (name "Net-(U200-+)") (class "Default")
      (node (ref "J106") (pin "19") (pinfunction "19_19") (pintype "passive"))
      (node (ref "U200") (pin "3") (pinfunction "+_3") (pintype "input"))
    )
    (net (code "79") (name "Net-(U200--)") (class "Default")
      (node (ref "R202") (pin "1") (pinfunction "1_1") (pintype "passive"))
      (node (ref "R203") (pin "2") (pinfunction "2_2") (pintype "passive"))
      (node (ref "U200") (pin "1") (pinfunction "-_1") (pintype "input"))
    )
    (net (code "80") (name "VCC") (class "Default")
      (node (ref "C101") (pin "1") (pinfunction "A_1") (pintype "input"))
      (node (ref "C102") (pin "1") (pinfunction "A_1") (pintype "input"))
      (node (ref "C105") (pin "2") (pinfunction "B_2") (pintype "input"))
      (node (ref "C107") (pin "1") (pinfunction "A_1") (pintype "input"))
      (node (ref "C108") (pin "1") (pinfunction "A_1") (pintype "input"))
      (node (ref "C109") (pin "1") (pinfunction "A_1") (pintype "input"))
      (node (ref "C125") (pin "1") (pinfunction "1_1") (pintype "passive"))
      (node (ref "D105") (pin "K") (pinfunction "K_K") (pintype "passive"))
      (node (ref "J105") (pin "8") (pinfunction "8_8") (pintype "passive"))
      (node (ref "R101") (pin "1") (pinfunction "A_1") (pintype "input"))
      (node (ref "R103") (pin "1") (pinfunction "A_1") (pintype "input"))
      (node (ref "R105") (pin "1") (pinfunction "A_1") (pintype "input"))
      (node (ref "R109") (pin "1") (pinfunction "A_1") (pintype "input"))
      (node (ref "R110") (pin "1") (pinfunction "A_1") (pintype "input"))
      (node (ref "R111") (pin "1") (pinfunction "A_1") (pintype "passive"))
      (node (ref "R118") (pin "1") (pinfunction "A_1") (pintype "input"))
      (node (ref "R119") (pin "1") (pinfunction "A_1") (pintype "input"))
      (node (ref "R130") (pin "2") (pinfunction "2_2") (pintype "passive"))
      (node (ref "R132") (pin "1") (pinfunction "A_1") (pintype "input"))
      (node (ref "R202") (pin "2") (pinfunction "2_2") (pintype "passive"))
      (node (ref "TP119") (pin "1") (pinfunction "TP_1") (pintype "passive"))
      (node (ref "TP123") (pin "1") (pinfunction "TP_1") (pintype "passive"))
      (node (ref "TP125") (pin "1") (pinfunction "TP_1") (pintype "passive"))
      (node (ref "U101") (pin "20") (pinfunction "Vdd_20") (pintype "input"))
      (node (ref "U102") (pin "20") (pinfunction "Vdd_20") (pintype "input"))
      (node (ref "U103") (pin "20") (pinfunction "Vdd_20") (pintype "input"))
      (node (ref "U104") (pin "16") (pinfunction "VCC_16") (pintype "passive"))
      (node (ref "U106") (pin "4") (pinfunction "VCC_4") (pintype "input"))
      (node (ref "U200") (pin "5") (pinfunction "VDD_5") (pintype "power_in"))
    )
    (net (code "81") (name "unconnected-(J106-Pad11)") (class "Default")
      (node (ref "J106") (pin "11") (pinfunction "11_11") (pintype "passive"))
    )
    (net (code "82") (name "unconnected-(J106-Pad12)") (class "Default")
      (node (ref "J106") (pin "12") (pinfunction "12_12") (pintype "passive"))
    )
    (net (code "83") (name "unconnected-(J106-Pad13)") (class "Default")
      (node (ref "J106") (pin "13") (pinfunction "13_13") (pintype "passive"))
    )
    (net (code "84") (name "unconnected-(J106-Pad14)") (class "Default")
      (node (ref "J106") (pin "14") (pinfunction "14_14") (pintype "passive"))
    )
    (net (code "85") (name "unconnected-(J106-Pad16)") (class "Default")
      (node (ref "J106") (pin "16") (pinfunction "16_16") (pintype "passive"))
    )
    (net (code "86") (name "unconnected-(J106-Pad17)") (class "Default")
      (node (ref "J106") (pin "17") (pinfunction "17_17") (pintype "passive"))
    )
    (net (code "87") (name "unconnected-(J106-Pad20)") (class "Default")
      (node (ref "J106") (pin "20") (pinfunction "20_20") (pintype "passive"))
    )
    (net (code "88") (name "unconnected-(J106-Pad21)") (class "Default")
      (node (ref "J106") (pin "21") (pinfunction "21_21") (pintype "passive"))
    )
    (net (code "89") (name "unconnected-(J106-Pad22)") (class "Default")
      (node (ref "J106") (pin "22") (pinfunction "22_22") (pintype "passive"))
    )
    (net (code "90") (name "unconnected-(J106-Pad23)") (class "Default")
      (node (ref "J106") (pin "23") (pinfunction "23_23") (pintype "passive"))
    )
    (net (code "91") (name "unconnected-(J106-Pad24)") (class "Default")
      (node (ref "J106") (pin "24") (pinfunction "24_24") (pintype "passive"))
    )
    (net (code "92") (name "unconnected-(J106-Pad25)") (class "Default")
      (node (ref "J106") (pin "25") (pinfunction "25_25") (pintype "passive"))
    )
    (net (code "93") (name "unconnected-(J106-Pad26)") (class "Default")
      (node (ref "J106") (pin "26") (pinfunction "26_26") (pintype "passive"))
    )
    (net (code "94") (name "unconnected-(J106-Pad27)") (class "Default")
      (node (ref "J106") (pin "27") (pinfunction "27_27") (pintype "passive"))
    )
    (net (code "95") (name "unconnected-(J106-Pad28)") (class "Default")
      (node (ref "J106") (pin "28") (pinfunction "28_28") (pintype "passive"))
    )
    (net (code "96") (name "unconnected-(J106-Pad29)") (class "Default")
      (node (ref "J106") (pin "29") (pinfunction "29_29") (pintype "passive"))
    )
    (net (code "97") (name "unconnected-(J106-Pad30)") (class "Default")
      (node (ref "J106") (pin "30") (pinfunction "30_30") (pintype "passive"))
    )
    (net (code "98") (name "unconnected-(J106-Pad31)") (class "Default")
      (node (ref "J106") (pin "31") (pinfunction "31_31") (pintype "passive"))
    )
    (net (code "99") (name "unconnected-(J106-Pad32)") (class "Default")
      (node (ref "J106") (pin "32") (pinfunction "32_32") (pintype "passive"))
    )
    (net (code "100") (name "unconnected-(J106-Pad33)") (class "Default")
      (node (ref "J106") (pin "33") (pinfunction "33_33") (pintype "passive"))
    )
    (net (code "101") (name "unconnected-(J106-Pad34)") (class "Default")
      (node (ref "J106") (pin "34") (pinfunction "34_34") (pintype "passive"))
    )
    (net (code "102") (name "unconnected-(J106-Pad35)") (class "Default")
      (node (ref "J106") (pin "35") (pinfunction "35_35") (pintype "passive"))
    )
    (net (code "103") (name "unconnected-(J106-Pad36)") (class "Default")
      (node (ref "J106") (pin "36") (pinfunction "36_36") (pintype "passive"))
    )
    (net (code "104") (name "unconnected-(J106-Pad37)") (class "Default")
      (node (ref "J106") (pin "37") (pinfunction "37_37") (pintype "passive"))
    )
    (net (code "105") (name "unconnected-(J106-Pad38)") (class "Default")
      (node (ref "J106") (pin "38") (pinfunction "38_38") (pintype "passive"))
    )
    (net (code "106") (name "unconnected-(J106-Pad39)") (class "Default")
      (node (ref "J106") (pin "39") (pinfunction "39_39") (pintype "passive"))
    )
    (net (code "107") (name "unconnected-(J106-Pad40)") (class "Default")
      (node (ref "J106") (pin "40") (pinfunction "40_40") (pintype "passive"))
    )
    (net (code "108") (name "unconnected-(U101-OSC2{slash}CLKOUT-Pad10)") (class "Default")
      (node (ref "U101") (pin "10") (pinfunction "OSC2/CLKOUT_10") (pintype "input"))
    )
    (net (code "109") (name "unconnected-(U101-RA5{slash}AN4-Pad7)") (class "Default")
      (node (ref "U101") (pin "7") (pinfunction "RA5/AN4_7") (pintype "input"))
    )
    (net (code "110") (name "unconnected-(U101-RB1-Pad22)") (class "Default")
      (node (ref "U101") (pin "22") (pinfunction "RB1_22") (pintype "input"))
    )
    (net (code "111") (name "unconnected-(U102-OSC2{slash}CLKOUT-Pad10)") (class "Default")
      (node (ref "U102") (pin "10") (pinfunction "OSC2/CLKOUT_10") (pintype "input"))
    )
    (net (code "112") (name "unconnected-(U103-OSC2{slash}CLKOUT-Pad10)") (class "Default")
      (node (ref "U103") (pin "10") (pinfunction "OSC2/CLKOUT_10") (pintype "input"))
    )
    (net (code "113") (name "unconnected-(U103-RC0{slash}T1OSO{slash}T1CKI-Pad11)") (class "Default")
      (node (ref "U103") (pin "11") (pinfunction "RC0/T1OSO/T1CKI_11") (pintype "input"))
    )
    (net (code "114") (name "unconnected-(U103-RC1{slash}T1OSI-Pad12)") (class "Default")
      (node (ref "U103") (pin "12") (pinfunction "RC1/T1OSI_12") (pintype "input"))
    )
    (net (code "115") (name "unconnected-(U103-RC6{slash}TX{slash}CK-Pad17)") (class "Default")
      (node (ref "U103") (pin "17") (pinfunction "RC6/TX/CK_17") (pintype "input"))
    )
    (net (code "116") (name "unconnected-(U106-OE-Pad1)") (class "Default")
      (node (ref "U106") (pin "1") (pinfunction "OE_1") (pintype "input"))
    )
  )
)
